# Breakout_UVC.net
KiCad netlist of a schematic drawn in EAGLE
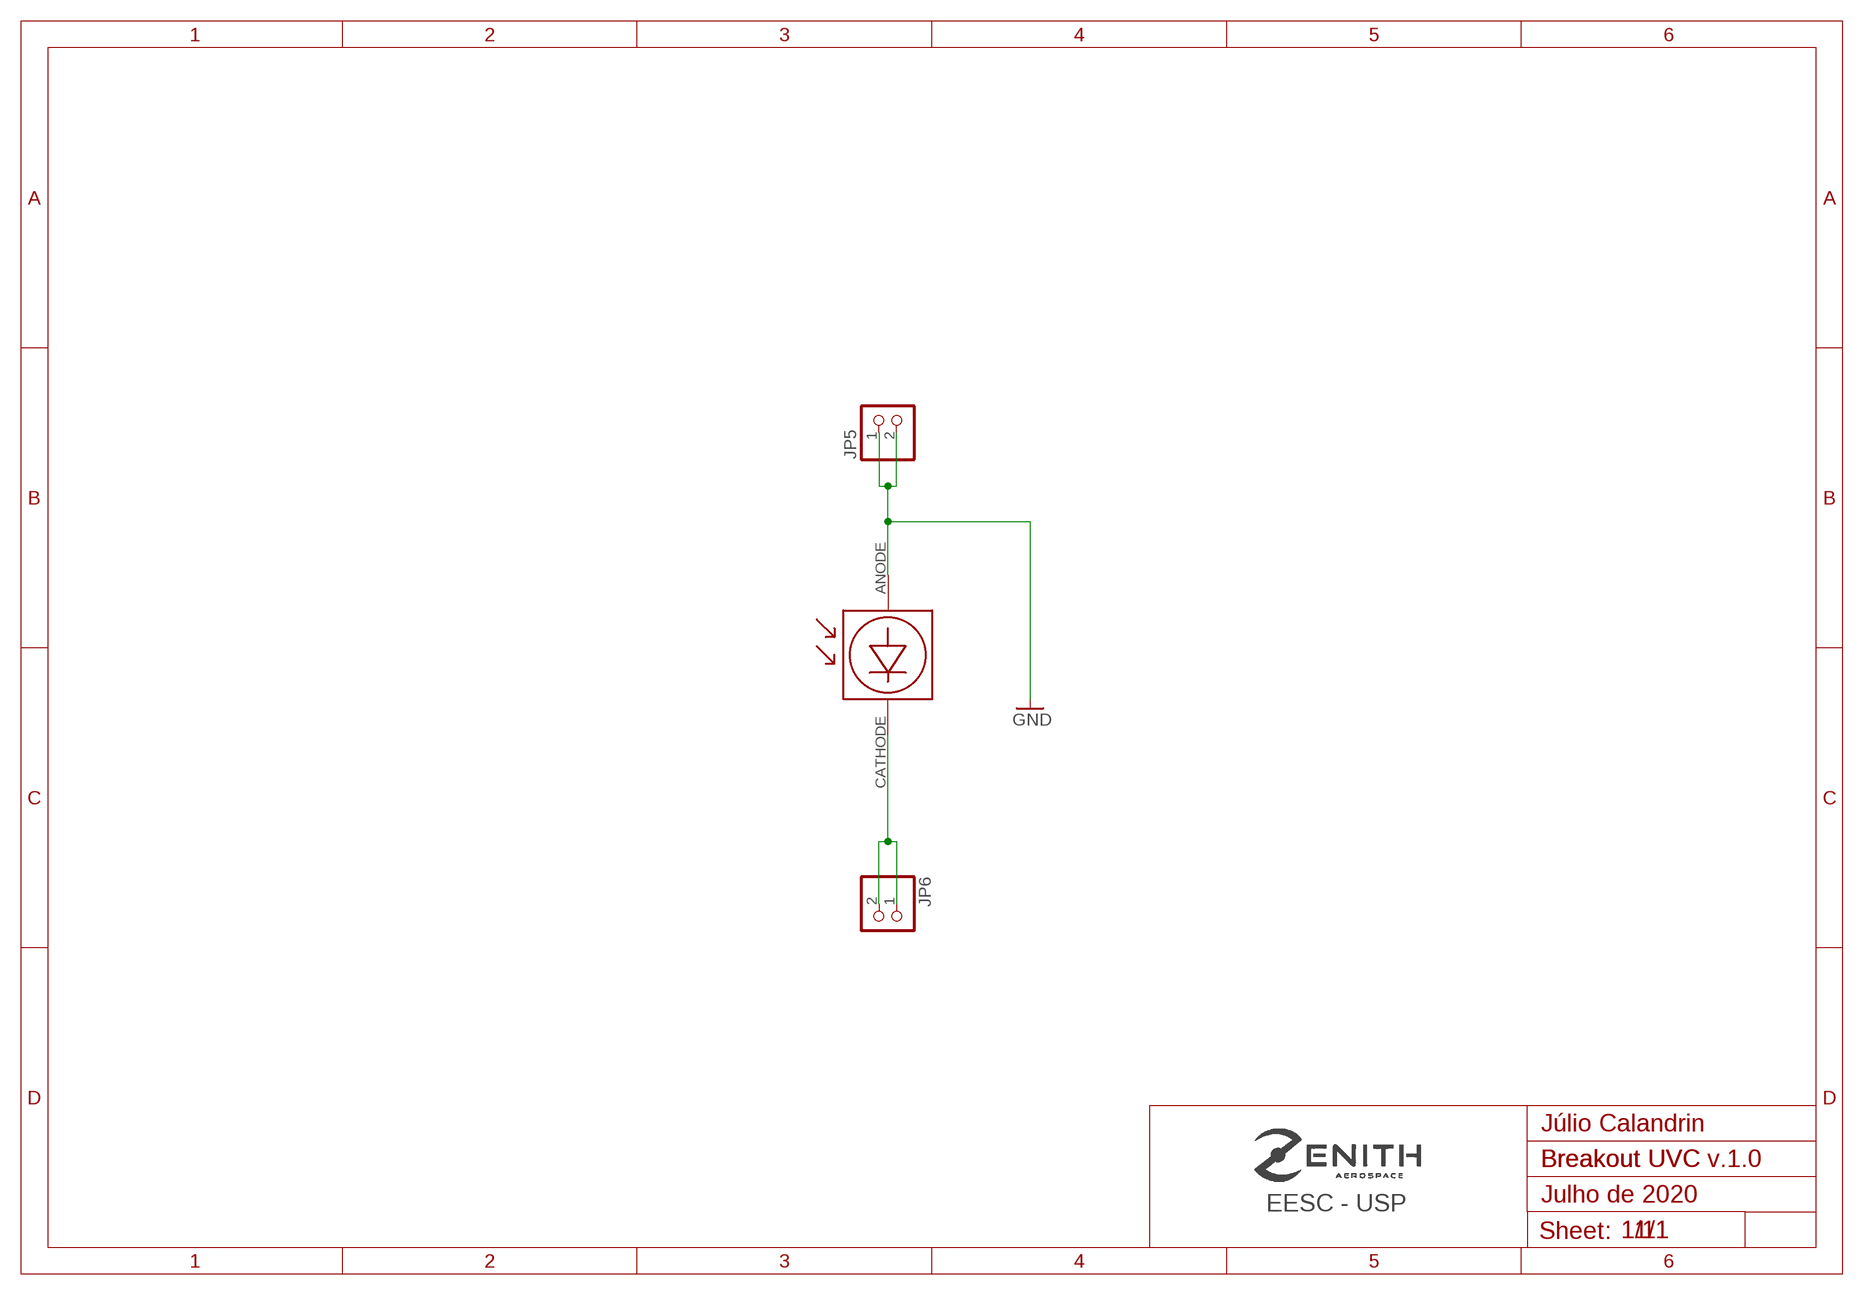
[diagram p0: schematic, sheet 1]

(export (version "E")
  (design (tool "Eeschema 10.0.6"))
  (components
    (comp (ref "JP5")
      (value "PINHD-1X2")
      (footprint "eagle-import:1X02")
      (libsource (lib "eagle-import") (part "PINHD-1X2"))
    )
    (comp (ref "JP6")
      (value "PINHD-1X2")
      (footprint "eagle-import:1X02")
      (libsource (lib "eagle-import") (part "PINHD-1X2"))
    )
    (comp (ref "U$1")
      (value "GUVC-S10GD")
      (footprint "eagle-import:GUV_C")
      (libsource (lib "eagle-import") (part "GUVC-S10GD"))
    )
  )
  (nets
    (net (code "1") (name "GND") (class "Default")
      (node (ref "JP5") (pin "1") (pinfunction "1_1") (pintype "passive"))
      (node (ref "JP5") (pin "2") (pinfunction "2_2") (pintype "passive"))
      (node (ref "U$1") (pin "ANODE") (pinfunction "ANODE_ANODE") (pintype "bidirectional"))
    )
    (net (code "2") (name "Net-(JP6-Pad1)") (class "Default")
      (node (ref "JP6") (pin "1") (pinfunction "1_1") (pintype "passive"))
      (node (ref "JP6") (pin "2") (pinfunction "2_2") (pintype "passive"))
      (node (ref "U$1") (pin "CATHODE") (pinfunction "CATHODE_CATHODE") (pintype "bidirectional"))
    )
  )
)
